# right_revision1_0.net
KiCad netlist of a schematic drawn in EAGLE
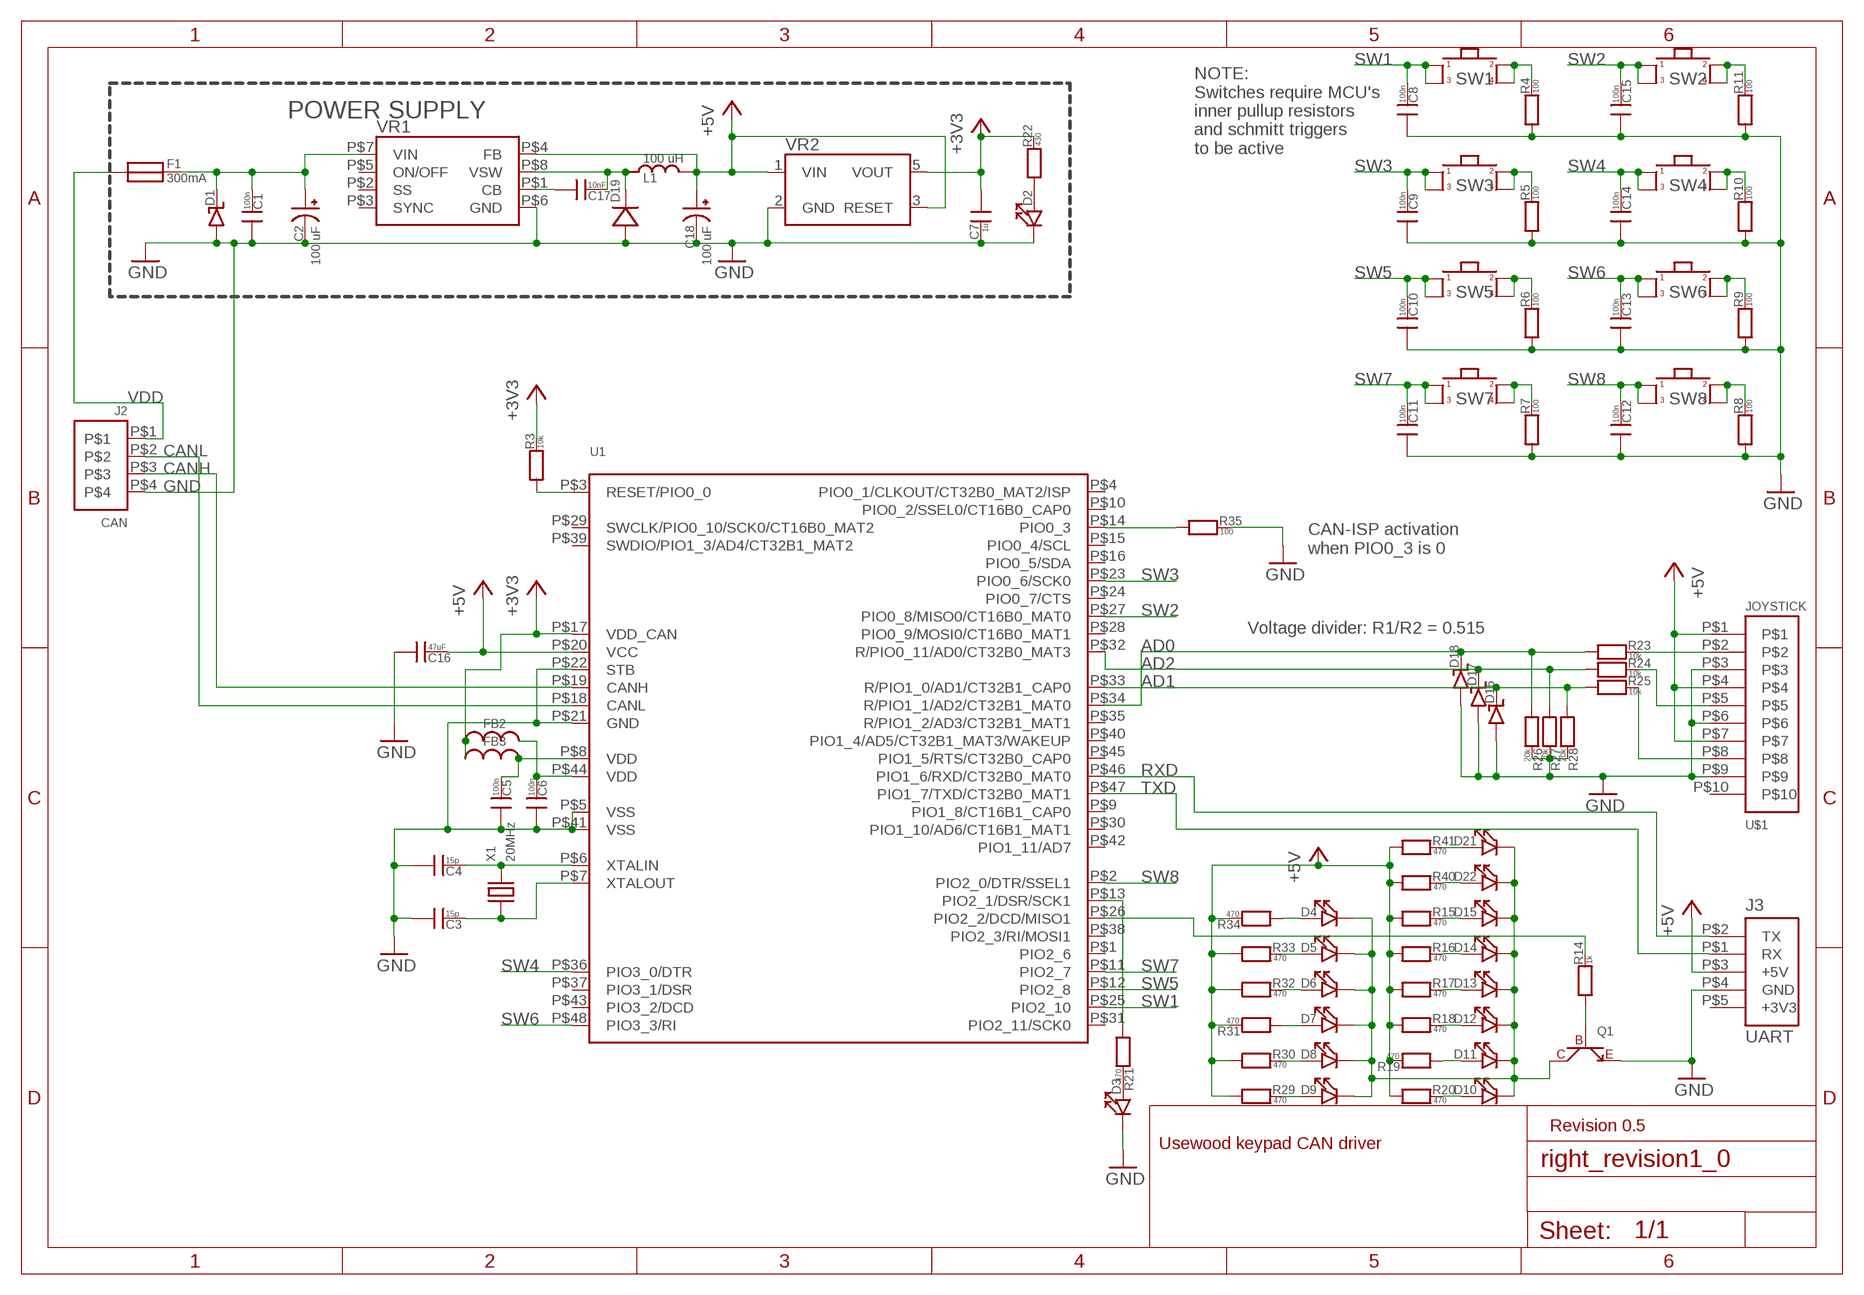
[diagram p0: schematic, sheet 1]

(export (version "E")
  (design (tool "Eeschema 10.0.6"))
  (components
    (comp (ref "C1")
      (value "100n")
      (footprint "eagle-import:0603_SILKSCREEN")
      (libsource (lib "eagle-import") (part "CAP0603_SILKSCREEN"))
    )
    (comp (ref "C2")
      (value "100 uF")
      (footprint "eagle-import:CAP_POL_SMD_10X10X10MM")
      (libsource (lib "eagle-import") (part "CAP_POLSMD_10X10X10MM"))
    )
    (comp (ref "C3")
      (value "15p")
      (footprint "eagle-import:0603_SILKSCREEN")
      (libsource (lib "eagle-import") (part "CAP0603_SILKSCREEN"))
    )
    (comp (ref "C4")
      (value "15p")
      (footprint "eagle-import:0603_SILKSCREEN")
      (libsource (lib "eagle-import") (part "CAP0603_SILKSCREEN"))
    )
    (comp (ref "C5")
      (value "100n")
      (footprint "eagle-import:0603_SILKSCREEN")
      (libsource (lib "eagle-import") (part "CAP0603_SILKSCREEN"))
    )
    (comp (ref "C6")
      (value "100n")
      (footprint "eagle-import:0603_SILKSCREEN")
      (libsource (lib "eagle-import") (part "CAP0603_SILKSCREEN"))
    )
    (comp (ref "C7")
      (value "1u")
      (footprint "eagle-import:0603_SILKSCREEN")
      (libsource (lib "eagle-import") (part "CAP0603_SILKSCREEN"))
    )
    (comp (ref "C8")
      (value "100n")
      (footprint "eagle-import:0603_SILKSCREEN")
      (libsource (lib "eagle-import") (part "CAP0603_SILKSCREEN"))
    )
    (comp (ref "C9")
      (value "100n")
      (footprint "eagle-import:0603_SILKSCREEN")
      (libsource (lib "eagle-import") (part "CAP0603_SILKSCREEN"))
    )
    (comp (ref "C10")
      (value "100n")
      (footprint "eagle-import:0603_SILKSCREEN")
      (libsource (lib "eagle-import") (part "CAP0603_SILKSCREEN"))
    )
    (comp (ref "C11")
      (value "100n")
      (footprint "eagle-import:0603_SILKSCREEN")
      (libsource (lib "eagle-import") (part "CAP0603_SILKSCREEN"))
    )
    (comp (ref "C12")
      (value "100n")
      (footprint "eagle-import:0603_SILKSCREEN")
      (libsource (lib "eagle-import") (part "CAP0603_SILKSCREEN"))
    )
    (comp (ref "C13")
      (value "100n")
      (footprint "eagle-import:0603_SILKSCREEN")
      (libsource (lib "eagle-import") (part "CAP0603_SILKSCREEN"))
    )
    (comp (ref "C14")
      (value "100n")
      (footprint "eagle-import:0603_SILKSCREEN")
      (libsource (lib "eagle-import") (part "CAP0603_SILKSCREEN"))
    )
    (comp (ref "C15")
      (value "100n")
      (footprint "eagle-import:0603_SILKSCREEN")
      (libsource (lib "eagle-import") (part "CAP0603_SILKSCREEN"))
    )
    (comp (ref "C16")
      (value "47uF")
      (footprint "eagle-import:0603_SILKSCREEN")
      (libsource (lib "eagle-import") (part "CAP0603_SILKSCREEN"))
    )
    (comp (ref "C17")
      (value "10nF")
      (footprint "eagle-import:0603_SILKSCREEN")
      (libsource (lib "eagle-import") (part "CAP0603_SILKSCREEN"))
    )
    (comp (ref "C18")
      (value "100 uF")
      (footprint "eagle-import:CAP_POL_SMD_10X10X10MM")
      (libsource (lib "eagle-import") (part "CAP_POLSMD_10X10X10MM"))
    )
    (comp (ref "D1")
      (value "DIODE_TVSDO-214AA")
      (footprint "eagle-import:DO-214AB")
      (libsource (lib "eagle-import") (part "DIODE_TVSDO-214AA"))
    )
    (comp (ref "D2")
      (value "LED0603_SILKSCREEN")
      (footprint "eagle-import:0603_SILKSCREEN")
      (libsource (lib "eagle-import") (part "LED0603_SILKSCREEN"))
    )
    (comp (ref "D3")
      (value "LED0603_SILKSCREEN")
      (footprint "eagle-import:0603_SILKSCREEN")
      (libsource (lib "eagle-import") (part "LED0603_SILKSCREEN"))
    )
    (comp (ref "D4")
      (value "LED0603_SILKSCREEN")
      (footprint "eagle-import:0603_SILKSCREEN")
      (libsource (lib "eagle-import") (part "LED0603_SILKSCREEN"))
    )
    (comp (ref "D5")
      (value "LED0603_SILKSCREEN")
      (footprint "eagle-import:0603_SILKSCREEN")
      (libsource (lib "eagle-import") (part "LED0603_SILKSCREEN"))
    )
    (comp (ref "D6")
      (value "LED0603_SILKSCREEN")
      (footprint "eagle-import:0603_SILKSCREEN")
      (libsource (lib "eagle-import") (part "LED0603_SILKSCREEN"))
    )
    (comp (ref "D7")
      (value "LED0603_SILKSCREEN")
      (footprint "eagle-import:0603_SILKSCREEN")
      (libsource (lib "eagle-import") (part "LED0603_SILKSCREEN"))
    )
    (comp (ref "D8")
      (value "LED0603_SILKSCREEN")
      (footprint "eagle-import:0603_SILKSCREEN")
      (libsource (lib "eagle-import") (part "LED0603_SILKSCREEN"))
    )
    (comp (ref "D9")
      (value "LED0603_SILKSCREEN")
      (footprint "eagle-import:0603_SILKSCREEN")
      (libsource (lib "eagle-import") (part "LED0603_SILKSCREEN"))
    )
    (comp (ref "D10")
      (value "LED0603_SILKSCREEN")
      (footprint "eagle-import:0603_SILKSCREEN")
      (libsource (lib "eagle-import") (part "LED0603_SILKSCREEN"))
    )
    (comp (ref "D11")
      (value "LED0603_SILKSCREEN")
      (footprint "eagle-import:0603_SILKSCREEN")
      (libsource (lib "eagle-import") (part "LED0603_SILKSCREEN"))
    )
    (comp (ref "D12")
      (value "LED0603_SILKSCREEN")
      (footprint "eagle-import:0603_SILKSCREEN")
      (libsource (lib "eagle-import") (part "LED0603_SILKSCREEN"))
    )
    (comp (ref "D13")
      (value "LED0603_SILKSCREEN")
      (footprint "eagle-import:0603_SILKSCREEN")
      (libsource (lib "eagle-import") (part "LED0603_SILKSCREEN"))
    )
    (comp (ref "D14")
      (value "LED0603_SILKSCREEN")
      (footprint "eagle-import:0603_SILKSCREEN")
      (libsource (lib "eagle-import") (part "LED0603_SILKSCREEN"))
    )
    (comp (ref "D15")
      (value "LED0603_SILKSCREEN")
      (footprint "eagle-import:0603_SILKSCREEN")
      (libsource (lib "eagle-import") (part "LED0603_SILKSCREEN"))
    )
    (comp (ref "D16")
      (value "DIODE_ZENERSDO123")
      (footprint "eagle-import:SOD123")
      (libsource (lib "eagle-import") (part "DIODE_ZENERSDO123"))
    )
    (comp (ref "D17")
      (value "DIODE_ZENERSDO123")
      (footprint "eagle-import:SOD123")
      (libsource (lib "eagle-import") (part "DIODE_ZENERSDO123"))
    )
    (comp (ref "D18")
      (value "DIODE_ZENERSDO123")
      (footprint "eagle-import:SOD123")
      (libsource (lib "eagle-import") (part "DIODE_ZENERSDO123"))
    )
    (comp (ref "D19")
      (value "DIODEDO219AB")
      (footprint "eagle-import:DO219AB")
      (libsource (lib "eagle-import") (part "DIODEDO219AB"))
    )
    (comp (ref "D21")
      (value "LED0603_SILKSCREEN")
      (footprint "eagle-import:0603_SILKSCREEN")
      (libsource (lib "eagle-import") (part "LED0603_SILKSCREEN"))
    )
    (comp (ref "D22")
      (value "LED0603_SILKSCREEN")
      (footprint "eagle-import:0603_SILKSCREEN")
      (libsource (lib "eagle-import") (part "LED0603_SILKSCREEN"))
    )
    (comp (ref "F1")
      (value "300mA")
      (footprint "eagle-import:FUSE_100MA")
      (libsource (lib "eagle-import") (part "FUSE100MA"))
    )
    (comp (ref "FB2")
      (value "FERRITE0603_SILKSCREEN")
      (footprint "eagle-import:0603_SILKSCREEN")
      (libsource (lib "eagle-import") (part "FERRITE0603_SILKSCREEN"))
    )
    (comp (ref "FB3")
      (value "FERRITE0603_SILKSCREEN")
      (footprint "eagle-import:0603_SILKSCREEN")
      (libsource (lib "eagle-import") (part "FERRITE0603_SILKSCREEN"))
    )
    (comp (ref "J2")
      (value "CAN")
      (footprint "eagle-import:MOLEX_MICRO-FIT_4WAY")
      (libsource (lib "eagle-import") (part "MOLEX_MICRO-FIT_4WAYTH"))
    )
    (comp (ref "J3")
      (value "UART")
      (footprint "eagle-import:HEADER5_1")
      (libsource (lib "eagle-import") (part "HEADER_USARTTH"))
    )
    (comp (ref "L1")
      (value "100 uH")
      (footprint "eagle-import:INDUCTOR_BOURNS_10X13X5MM")
      (libsource (lib "eagle-import") (part "INDUCTORBOURNS_10X13X5MM"))
    )
    (comp (ref "Q1")
      (value "NPN_TRANSISTORSOT323")
      (footprint "eagle-import:SOT323")
      (libsource (lib "eagle-import") (part "NPN_TRANSISTORSOT323"))
    )
    (comp (ref "R3")
      (value "10k")
      (footprint "eagle-import:0603_SILKSCREEN")
      (libsource (lib "eagle-import") (part "RES0604_SILKSCREEN"))
    )
    (comp (ref "R4")
      (value "100")
      (footprint "eagle-import:0603_SILKSCREEN")
      (libsource (lib "eagle-import") (part "RES0604_SILKSCREEN"))
    )
    (comp (ref "R5")
      (value "100")
      (footprint "eagle-import:0603_SILKSCREEN")
      (libsource (lib "eagle-import") (part "RES0604_SILKSCREEN"))
    )
    (comp (ref "R6")
      (value "100")
      (footprint "eagle-import:0603_SILKSCREEN")
      (libsource (lib "eagle-import") (part "RES0604_SILKSCREEN"))
    )
    (comp (ref "R7")
      (value "100")
      (footprint "eagle-import:0603_SILKSCREEN")
      (libsource (lib "eagle-import") (part "RES0604_SILKSCREEN"))
    )
    (comp (ref "R8")
      (value "100")
      (footprint "eagle-import:0603_SILKSCREEN")
      (libsource (lib "eagle-import") (part "RES0604_SILKSCREEN"))
    )
    (comp (ref "R9")
      (value "100")
      (footprint "eagle-import:0603_SILKSCREEN")
      (libsource (lib "eagle-import") (part "RES0604_SILKSCREEN"))
    )
    (comp (ref "R10")
      (value "100")
      (footprint "eagle-import:0603_SILKSCREEN")
      (libsource (lib "eagle-import") (part "RES0604_SILKSCREEN"))
    )
    (comp (ref "R11")
      (value "100")
      (footprint "eagle-import:0603_SILKSCREEN")
      (libsource (lib "eagle-import") (part "RES0604_SILKSCREEN"))
    )
    (comp (ref "R14")
      (value "1k")
      (footprint "eagle-import:0603_SILKSCREEN")
      (libsource (lib "eagle-import") (part "RES0604_SILKSCREEN"))
    )
    (comp (ref "R15")
      (value "470")
      (footprint "eagle-import:0603_SILKSCREEN")
      (libsource (lib "eagle-import") (part "RES0604_SILKSCREEN"))
    )
    (comp (ref "R16")
      (value "470")
      (footprint "eagle-import:0603_SILKSCREEN")
      (libsource (lib "eagle-import") (part "RES0604_SILKSCREEN"))
    )
    (comp (ref "R17")
      (value "470")
      (footprint "eagle-import:0603_SILKSCREEN")
      (libsource (lib "eagle-import") (part "RES0604_SILKSCREEN"))
    )
    (comp (ref "R18")
      (value "470")
      (footprint "eagle-import:0603_SILKSCREEN")
      (libsource (lib "eagle-import") (part "RES0604_SILKSCREEN"))
    )
    (comp (ref "R19")
      (value "470")
      (footprint "eagle-import:0603_SILKSCREEN")
      (libsource (lib "eagle-import") (part "RES0604_SILKSCREEN"))
    )
    (comp (ref "R20")
      (value "470")
      (footprint "eagle-import:0603_SILKSCREEN")
      (libsource (lib "eagle-import") (part "RES0604_SILKSCREEN"))
    )
    (comp (ref "R21")
      (value "470")
      (footprint "eagle-import:0603_SILKSCREEN")
      (libsource (lib "eagle-import") (part "RES0604_SILKSCREEN"))
    )
    (comp (ref "R22")
      (value "430")
      (footprint "eagle-import:0603_SILKSCREEN")
      (libsource (lib "eagle-import") (part "RES0604_SILKSCREEN"))
    )
    (comp (ref "R23")
      (value "10k")
      (footprint "eagle-import:0603_SILKSCREEN")
      (libsource (lib "eagle-import") (part "RES0604_SILKSCREEN"))
    )
    (comp (ref "R24")
      (value "10k")
      (footprint "eagle-import:0603_SILKSCREEN")
      (libsource (lib "eagle-import") (part "RES0604_SILKSCREEN"))
    )
    (comp (ref "R25")
      (value "10k")
      (footprint "eagle-import:0603_SILKSCREEN")
      (libsource (lib "eagle-import") (part "RES0604_SILKSCREEN"))
    )
    (comp (ref "R26")
      (value "20k")
      (footprint "eagle-import:0603_SILKSCREEN")
      (libsource (lib "eagle-import") (part "RES0604_SILKSCREEN"))
    )
    (comp (ref "R27")
      (value "20k")
      (footprint "eagle-import:0603_SILKSCREEN")
      (libsource (lib "eagle-import") (part "RES0604_SILKSCREEN"))
    )
    (comp (ref "R28")
      (value "20k")
      (footprint "eagle-import:0603_SILKSCREEN")
      (libsource (lib "eagle-import") (part "RES0604_SILKSCREEN"))
    )
    (comp (ref "R29")
      (value "470")
      (footprint "eagle-import:0603_SILKSCREEN")
      (libsource (lib "eagle-import") (part "RES0604_SILKSCREEN"))
    )
    (comp (ref "R30")
      (value "470")
      (footprint "eagle-import:0603_SILKSCREEN")
      (libsource (lib "eagle-import") (part "RES0604_SILKSCREEN"))
    )
    (comp (ref "R31")
      (value "470")
      (footprint "eagle-import:0603_SILKSCREEN")
      (libsource (lib "eagle-import") (part "RES0604_SILKSCREEN"))
    )
    (comp (ref "R32")
      (value "470")
      (footprint "eagle-import:0603_SILKSCREEN")
      (libsource (lib "eagle-import") (part "RES0604_SILKSCREEN"))
    )
    (comp (ref "R33")
      (value "470")
      (footprint "eagle-import:0603_SILKSCREEN")
      (libsource (lib "eagle-import") (part "RES0604_SILKSCREEN"))
    )
    (comp (ref "R34")
      (value "470")
      (footprint "eagle-import:0603_SILKSCREEN")
      (libsource (lib "eagle-import") (part "RES0604_SILKSCREEN"))
    )
    (comp (ref "R35")
      (value "100")
      (footprint "eagle-import:0603_SILKSCREEN")
      (libsource (lib "eagle-import") (part "RES0604_SILKSCREEN"))
    )
    (comp (ref "R40")
      (value "470")
      (footprint "eagle-import:0603_SILKSCREEN")
      (libsource (lib "eagle-import") (part "RES0604_SILKSCREEN"))
    )
    (comp (ref "R41")
      (value "470")
      (footprint "eagle-import:0603_SILKSCREEN")
      (libsource (lib "eagle-import") (part "RES0604_SILKSCREEN"))
    )
    (comp (ref "SW1")
      (value "SWITCH12X12MM_CENTER_HOLE")
      (footprint "eagle-import:SWITCH_12X12MM_CENTER_HOLE")
      (libsource (lib "eagle-import") (part "SWITCH12X12MM_CENTER_HOLE"))
    )
    (comp (ref "SW2")
      (value "SWITCH12X12MM_CENTER_HOLE")
      (footprint "eagle-import:SWITCH_12X12MM_CENTER_HOLE")
      (libsource (lib "eagle-import") (part "SWITCH12X12MM_CENTER_HOLE"))
    )
    (comp (ref "SW3")
      (value "SWITCH12X12MM_CENTER_HOLE")
      (footprint "eagle-import:SWITCH_12X12MM_CENTER_HOLE")
      (libsource (lib "eagle-import") (part "SWITCH12X12MM_CENTER_HOLE"))
    )
    (comp (ref "SW4")
      (value "SWITCH12X12MM_CENTER_HOLE")
      (footprint "eagle-import:SWITCH_12X12MM_CENTER_HOLE")
      (libsource (lib "eagle-import") (part "SWITCH12X12MM_CENTER_HOLE"))
    )
    (comp (ref "SW5")
      (value "SWITCH12X12MM_CENTER_HOLE")
      (footprint "eagle-import:SWITCH_12X12MM_CENTER_HOLE")
      (libsource (lib "eagle-import") (part "SWITCH12X12MM_CENTER_HOLE"))
    )
    (comp (ref "SW6")
      (value "SWITCH12X12MM_CENTER_HOLE")
      (footprint "eagle-import:SWITCH_12X12MM_CENTER_HOLE")
      (libsource (lib "eagle-import") (part "SWITCH12X12MM_CENTER_HOLE"))
    )
    (comp (ref "SW7")
      (value "SWITCH12X12MM_CENTER_HOLE")
      (footprint "eagle-import:SWITCH_12X12MM_CENTER_HOLE")
      (libsource (lib "eagle-import") (part "SWITCH12X12MM_CENTER_HOLE"))
    )
    (comp (ref "SW8")
      (value "SWITCH12X12MM_CENTER_HOLE")
      (footprint "eagle-import:SWITCH_12X12MM_CENTER_HOLE")
      (libsource (lib "eagle-import") (part "SWITCH12X12MM_CENTER_HOLE"))
    )
    (comp (ref "U$1")
      (value "JOYSTICK")
      (footprint "eagle-import:MOLEX-MICRO-FIT_10WAY")
      (libsource (lib "eagle-import") (part "MOLEX_MICRO-FIT_10WAYTH"))
    )
    (comp (ref "U1")
      (value "LPC11C22QFP48")
      (footprint "eagle-import:QFP48")
      (libsource (lib "eagle-import") (part "LPC11C22QFP48"))
    )
    (comp (ref "VR1")
      (value "LM2671SOIC8")
      (footprint "eagle-import:SOIC8")
      (libsource (lib "eagle-import") (part "LM2671SOIC8"))
    )
    (comp (ref "VR2")
      (value "LP2985SOP5")
      (footprint "eagle-import:SOP5")
      (libsource (lib "eagle-import") (part "LP2985SOP5"))
    )
    (comp (ref "X1")
      (value "20MHz")
      (footprint "eagle-import:XTAL_SMD_5X3.2")
      (libsource (lib "eagle-import") (part "XTALSMD_5X3.2"))
    )
  )
  (nets
    (net (code "1") (name "+3V3") (class "Default")
      (node (ref "C7") (pin "0") (pinfunction "P$1_0") (pintype "bidirectional"))
      (node (ref "FB2") (pin "0") (pinfunction "P$1_0") (pintype "bidirectional"))
      (node (ref "FB3") (pin "0") (pinfunction "P$1_0") (pintype "bidirectional"))
      (node (ref "R22") (pin "1") (pinfunction "P$2_1") (pintype "bidirectional"))
      (node (ref "R3") (pin "1") (pinfunction "P$2_1") (pintype "bidirectional"))
      (node (ref "U1") (pin "P$17") (pinfunction "VDD_CAN_P$17") (pintype "bidirectional"))
      (node (ref "VR2") (pin "5") (pinfunction "VOUT_5") (pintype "bidirectional"))
    )
    (net (code "2") (name "+5V") (class "Default")
      (node (ref "C16") (pin "1") (pinfunction "P$2_1") (pintype "bidirectional"))
      (node (ref "C18") (pin "+") (pinfunction "+_+") (pintype "bidirectional"))
      (node (ref "J3") (pin "P$3") (pinfunction "+5V_P$3") (pintype "bidirectional"))
      (node (ref "L1") (pin "P$2") (pinfunction "P$2_P$2") (pintype "bidirectional"))
      (node (ref "R15") (pin "0") (pinfunction "P$1_0") (pintype "bidirectional"))
      (node (ref "R16") (pin "0") (pinfunction "P$1_0") (pintype "bidirectional"))
      (node (ref "R17") (pin "0") (pinfunction "P$1_0") (pintype "bidirectional"))
      (node (ref "R18") (pin "0") (pinfunction "P$1_0") (pintype "bidirectional"))
      (node (ref "R19") (pin "1") (pinfunction "P$2_1") (pintype "bidirectional"))
      (node (ref "R20") (pin "0") (pinfunction "P$1_0") (pintype "bidirectional"))
      (node (ref "R29") (pin "0") (pinfunction "P$1_0") (pintype "bidirectional"))
      (node (ref "R30") (pin "0") (pinfunction "P$1_0") (pintype "bidirectional"))
      (node (ref "R31") (pin "1") (pinfunction "P$2_1") (pintype "bidirectional"))
      (node (ref "R32") (pin "0") (pinfunction "P$1_0") (pintype "bidirectional"))
      (node (ref "R33") (pin "0") (pinfunction "P$1_0") (pintype "bidirectional"))
      (node (ref "R34") (pin "1") (pinfunction "P$2_1") (pintype "bidirectional"))
      (node (ref "R40") (pin "0") (pinfunction "P$1_0") (pintype "bidirectional"))
      (node (ref "R41") (pin "0") (pinfunction "P$1_0") (pintype "bidirectional"))
      (node (ref "U$1") (pin "P$1") (pinfunction "P$1_P$1") (pintype "bidirectional"))
      (node (ref "U$1") (pin "P$4") (pinfunction "P$4_P$4") (pintype "bidirectional"))
      (node (ref "U$1") (pin "P$7") (pinfunction "P$7_P$7") (pintype "bidirectional"))
      (node (ref "U1") (pin "P$20") (pinfunction "VCC_P$20") (pintype "bidirectional"))
      (node (ref "VR1") (pin "P$4") (pinfunction "FB_P$4") (pintype "bidirectional"))
      (node (ref "VR2") (pin "1") (pinfunction "VIN_1") (pintype "bidirectional"))
      (node (ref "VR2") (pin "3") (pinfunction "RESET_3") (pintype "bidirectional"))
    )
    (net (code "3") (name "/AD0") (class "Default")
      (node (ref "D18") (pin "P$2") (pinfunction "N_P$2") (pintype "bidirectional"))
      (node (ref "R23") (pin "0") (pinfunction "P$1_0") (pintype "bidirectional"))
      (node (ref "R26") (pin "0") (pinfunction "P$1_0") (pintype "bidirectional"))
      (node (ref "U1") (pin "P$34") (pinfunction "R/PIO1_1/AD2/CT32B1_MAT0_P$34") (pintype "bidirectional"))
    )
    (net (code "4") (name "/AD1") (class "Default")
      (node (ref "D16") (pin "P$2") (pinfunction "N_P$2") (pintype "bidirectional"))
      (node (ref "R25") (pin "0") (pinfunction "P$1_0") (pintype "bidirectional"))
      (node (ref "R28") (pin "0") (pinfunction "P$1_0") (pintype "bidirectional"))
      (node (ref "U1") (pin "P$33") (pinfunction "R/PIO1_0/AD1/CT32B1_CAP0_P$33") (pintype "bidirectional"))
    )
    (net (code "5") (name "/AD2") (class "Default")
      (node (ref "D17") (pin "P$2") (pinfunction "N_P$2") (pintype "bidirectional"))
      (node (ref "R24") (pin "0") (pinfunction "P$1_0") (pintype "bidirectional"))
      (node (ref "R27") (pin "0") (pinfunction "P$1_0") (pintype "bidirectional"))
      (node (ref "U1") (pin "P$32") (pinfunction "R/PIO0_11/AD0/CT32B0_MAT3_P$32") (pintype "bidirectional"))
    )
    (net (code "6") (name "/CANH") (class "Default")
      (node (ref "J2") (pin "P$3") (pinfunction "P$3_P$3") (pintype "bidirectional"))
      (node (ref "U1") (pin "P$19") (pinfunction "CANH_P$19") (pintype "bidirectional"))
    )
    (net (code "7") (name "/CANL") (class "Default")
      (node (ref "J2") (pin "P$2") (pinfunction "P$2_P$2") (pintype "bidirectional"))
      (node (ref "U1") (pin "P$18") (pinfunction "CANL_P$18") (pintype "bidirectional"))
    )
    (net (code "8") (name "/RXD") (class "Default")
      (node (ref "J3") (pin "P$2") (pinfunction "TX_P$2") (pintype "bidirectional"))
      (node (ref "U1") (pin "P$46") (pinfunction "PIO1_6/RXD/CT32B0_MAT0_P$46") (pintype "bidirectional"))
    )
    (net (code "9") (name "/SW1") (class "Default")
      (node (ref "C8") (pin "1") (pinfunction "P$2_1") (pintype "bidirectional"))
      (node (ref "SW1") (pin "P$1") (pinfunction "P$1_P$1") (pintype "bidirectional"))
      (node (ref "SW1") (pin "P$2") (pinfunction "P$3_P$2") (pintype "bidirectional"))
      (node (ref "U1") (pin "P$25") (pinfunction "PIO2_10_P$25") (pintype "bidirectional"))
    )
    (net (code "10") (name "/SW2") (class "Default")
      (node (ref "C15") (pin "1") (pinfunction "P$2_1") (pintype "bidirectional"))
      (node (ref "SW2") (pin "P$1") (pinfunction "P$1_P$1") (pintype "bidirectional"))
      (node (ref "SW2") (pin "P$2") (pinfunction "P$3_P$2") (pintype "bidirectional"))
      (node (ref "U1") (pin "P$27") (pinfunction "PIO0_8/MISO0/CT16B0_MAT0_P$27") (pintype "bidirectional"))
    )
    (net (code "11") (name "/SW3") (class "Default")
      (node (ref "C9") (pin "1") (pinfunction "P$2_1") (pintype "bidirectional"))
      (node (ref "SW3") (pin "P$1") (pinfunction "P$1_P$1") (pintype "bidirectional"))
      (node (ref "SW3") (pin "P$2") (pinfunction "P$3_P$2") (pintype "bidirectional"))
      (node (ref "U1") (pin "P$23") (pinfunction "PIO0_6/SCK0_P$23") (pintype "bidirectional"))
    )
    (net (code "12") (name "/SW4") (class "Default")
      (node (ref "C14") (pin "1") (pinfunction "P$2_1") (pintype "bidirectional"))
      (node (ref "SW4") (pin "P$1") (pinfunction "P$1_P$1") (pintype "bidirectional"))
      (node (ref "SW4") (pin "P$2") (pinfunction "P$3_P$2") (pintype "bidirectional"))
      (node (ref "U1") (pin "P$36") (pinfunction "PIO3_0/DTR_P$36") (pintype "bidirectional"))
    )
    (net (code "13") (name "/SW5") (class "Default")
      (node (ref "C10") (pin "1") (pinfunction "P$2_1") (pintype "bidirectional"))
      (node (ref "SW5") (pin "P$1") (pinfunction "P$1_P$1") (pintype "bidirectional"))
      (node (ref "SW5") (pin "P$2") (pinfunction "P$3_P$2") (pintype "bidirectional"))
      (node (ref "U1") (pin "P$12") (pinfunction "PIO2_8_P$12") (pintype "bidirectional"))
    )
    (net (code "14") (name "/SW6") (class "Default")
      (node (ref "C13") (pin "1") (pinfunction "P$2_1") (pintype "bidirectional"))
      (node (ref "SW6") (pin "P$1") (pinfunction "P$1_P$1") (pintype "bidirectional"))
      (node (ref "SW6") (pin "P$2") (pinfunction "P$3_P$2") (pintype "bidirectional"))
      (node (ref "U1") (pin "P$48") (pinfunction "PIO3_3/RI_P$48") (pintype "bidirectional"))
    )
    (net (code "15") (name "/SW7") (class "Default")
      (node (ref "C11") (pin "1") (pinfunction "P$2_1") (pintype "bidirectional"))
      (node (ref "SW7") (pin "P$1") (pinfunction "P$1_P$1") (pintype "bidirectional"))
      (node (ref "SW7") (pin "P$2") (pinfunction "P$3_P$2") (pintype "bidirectional"))
      (node (ref "U1") (pin "P$11") (pinfunction "PIO2_7_P$11") (pintype "bidirectional"))
    )
    (net (code "16") (name "/SW8") (class "Default")
      (node (ref "C12") (pin "1") (pinfunction "P$2_1") (pintype "bidirectional"))
      (node (ref "SW8") (pin "P$1") (pinfunction "P$1_P$1") (pintype "bidirectional"))
      (node (ref "SW8") (pin "P$2") (pinfunction "P$3_P$2") (pintype "bidirectional"))
      (node (ref "U1") (pin "P$2") (pinfunction "PIO2_0/DTR/SSEL1_P$2") (pintype "bidirectional"))
    )
    (net (code "17") (name "/TXD") (class "Default")
      (node (ref "J3") (pin "P$1") (pinfunction "RX_P$1") (pintype "bidirectional"))
      (node (ref "U1") (pin "P$47") (pinfunction "PIO1_7/TXD/CT32B0_MAT1_P$47") (pintype "bidirectional"))
    )
    (net (code "18") (name "/VDD") (class "Default")
      (node (ref "F1") (pin "P$1") (pinfunction "P$1_P$1") (pintype "bidirectional"))
      (node (ref "J2") (pin "P$1") (pinfunction "P$1_P$1") (pintype "bidirectional"))
    )
    (net (code "19") (name "GND") (class "Default")
      (node (ref "C1") (pin "0") (pinfunction "P$1_0") (pintype "bidirectional"))
      (node (ref "C10") (pin "0") (pinfunction "P$1_0") (pintype "bidirectional"))
      (node (ref "C11") (pin "0") (pinfunction "P$1_0") (pintype "bidirectional"))
      (node (ref "C12") (pin "0") (pinfunction "P$1_0") (pintype "bidirectional"))
      (node (ref "C13") (pin "0") (pinfunction "P$1_0") (pintype "bidirectional"))
      (node (ref "C14") (pin "0") (pinfunction "P$1_0") (pintype "bidirectional"))
      (node (ref "C15") (pin "0") (pinfunction "P$1_0") (pintype "bidirectional"))
      (node (ref "C16") (pin "0") (pinfunction "P$1_0") (pintype "bidirectional"))
      (node (ref "C18") (pin "-") (pinfunction "-_-") (pintype "bidirectional"))
      (node (ref "C2") (pin "-") (pinfunction "-_-") (pintype "bidirectional"))
      (node (ref "C3") (pin "0") (pinfunction "P$1_0") (pintype "bidirectional"))
      (node (ref "C4") (pin "0") (pinfunction "P$1_0") (pintype "bidirectional"))
      (node (ref "C5") (pin "0") (pinfunction "P$1_0") (pintype "bidirectional"))
      (node (ref "C6") (pin "0") (pinfunction "P$1_0") (pintype "bidirectional"))
      (node (ref "C7") (pin "1") (pinfunction "P$2_1") (pintype "bidirectional"))
      (node (ref "C8") (pin "0") (pinfunction "P$1_0") (pintype "bidirectional"))
      (node (ref "C9") (pin "0") (pinfunction "P$1_0") (pintype "bidirectional"))
      (node (ref "D1") (pin "P$1") (pinfunction "P_P$1") (pintype "bidirectional"))
      (node (ref "D16") (pin "P$1") (pinfunction "P_P$1") (pintype "bidirectional"))
      (node (ref "D17") (pin "P$1") (pinfunction "P_P$1") (pintype "bidirectional"))
      (node (ref "D18") (pin "P$1") (pinfunction "P_P$1") (pintype "bidirectional"))
      (node (ref "D19") (pin "P$1") (pinfunction "P_P$1") (pintype "bidirectional"))
      (node (ref "D2") (pin "1") (pinfunction "1_1") (pintype "bidirectional"))
      (node (ref "D3") (pin "1") (pinfunction "1_1") (pintype "bidirectional"))
      (node (ref "J2") (pin "P$4") (pinfunction "P$4_P$4") (pintype "bidirectional"))
      (node (ref "J3") (pin "P$4") (pinfunction "GND_P$4") (pintype "bidirectional"))
      (node (ref "Q1") (pin "R") (pinfunction "E_R") (pintype "bidirectional"))
      (node (ref "R10") (pin "0") (pinfunction "P$1_0") (pintype "bidirectional"))
      (node (ref "R11") (pin "0") (pinfunction "P$1_0") (pintype "bidirectional"))
      (node (ref "R26") (pin "1") (pinfunction "P$2_1") (pintype "bidirectional"))
      (node (ref "R27") (pin "1") (pinfunction "P$2_1") (pintype "bidirectional"))
      (node (ref "R28") (pin "1") (pinfunction "P$2_1") (pintype "bidirectional"))
      (node (ref "R35") (pin "1") (pinfunction "P$2_1") (pintype "bidirectional"))
      (node (ref "R4") (pin "0") (pinfunction "P$1_0") (pintype "bidirectional"))
      (node (ref "R5") (pin "0") (pinfunction "P$1_0") (pintype "bidirectional"))
      (node (ref "R6") (pin "0") (pinfunction "P$1_0") (pintype "bidirectional"))
      (node (ref "R7") (pin "0") (pinfunction "P$1_0") (pintype "bidirectional"))
      (node (ref "R8") (pin "0") (pinfunction "P$1_0") (pintype "bidirectional"))
      (node (ref "R9") (pin "0") (pinfunction "P$1_0") (pintype "bidirectional"))
      (node (ref "U$1") (pin "P$3") (pinfunction "P$3_P$3") (pintype "bidirectional"))
      (node (ref "U$1") (pin "P$6") (pinfunction "P$6_P$6") (pintype "bidirectional"))
      (node (ref "U$1") (pin "P$9") (pinfunction "P$9_P$9") (pintype "bidirectional"))
      (node (ref "U1") (pin "P$21") (pinfunction "GND_P$21") (pintype "bidirectional"))
      (node (ref "U1") (pin "P$22") (pinfunction "STB_P$22") (pintype "bidirectional"))
      (node (ref "U1") (pin "P$41") (pinfunction "VSS_P$41") (pintype "bidirectional"))
      (node (ref "U1") (pin "P$5") (pinfunction "VSS_P$5") (pintype "bidirectional"))
      (node (ref "VR1") (pin "P$6") (pinfunction "GND_P$6") (pintype "bidirectional"))
      (node (ref "VR2") (pin "2") (pinfunction "GND_2") (pintype "bidirectional"))
    )
    (net (code "20") (name "Net-(C1-P$2)") (class "Default")
      (node (ref "C1") (pin "1") (pinfunction "P$2_1") (pintype "bidirectional"))
      (node (ref "C2") (pin "+") (pinfunction "+_+") (pintype "bidirectional"))
      (node (ref "D1") (pin "P$2") (pinfunction "N_P$2") (pintype "bidirectional"))
      (node (ref "F1") (pin "P$2") (pinfunction "P$2_P$2") (pintype "bidirectional"))
      (node (ref "VR1") (pin "P$7") (pinfunction "VIN_P$7") (pintype "bidirectional"))
    )
    (net (code "21") (name "Net-(C3-P$2)") (class "Default")
      (node (ref "C3") (pin "1") (pinfunction "P$2_1") (pintype "bidirectional"))
      (node (ref "U1") (pin "P$7") (pinfunction "XTALOUT_P$7") (pintype "bidirectional"))
      (node (ref "X1") (pin "P$1") (pinfunction "P$1_P$1") (pintype "bidirectional"))
    )
    (net (code "22") (name "Net-(C4-P$2)") (class "Default")
      (node (ref "C4") (pin "1") (pinfunction "P$2_1") (pintype "bidirectional"))
      (node (ref "U1") (pin "P$6") (pinfunction "XTALIN_P$6") (pintype "bidirectional"))
      (node (ref "X1") (pin "P$2") (pinfunction "P$2_P$2") (pintype "bidirectional"))
    )
    (net (code "23") (name "Net-(C5-P$2)") (class "Default")
      (node (ref "C5") (pin "1") (pinfunction "P$2_1") (pintype "bidirectional"))
      (node (ref "FB3") (pin "1") (pinfunction "P$2_1") (pintype "bidirectional"))
      (node (ref "U1") (pin "P$8") (pinfunction "VDD_P$8") (pintype "bidirectional"))
    )
    (net (code "24") (name "Net-(C6-P$2)") (class "Default")
      (node (ref "C6") (pin "1") (pinfunction "P$2_1") (pintype "bidirectional"))
      (node (ref "FB2") (pin "1") (pinfunction "P$2_1") (pintype "bidirectional"))
      (node (ref "U1") (pin "P$44") (pinfunction "VDD_P$44") (pintype "bidirectional"))
    )
    (net (code "25") (name "Net-(C17-P$1)") (class "Default")
      (node (ref "C17") (pin "0") (pinfunction "P$1_0") (pintype "bidirectional"))
      (node (ref "VR1") (pin "P$1") (pinfunction "CB_P$1") (pintype "bidirectional"))
    )
    (net (code "26") (name "Net-(C17-P$2)") (class "Default")
      (node (ref "C17") (pin "1") (pinfunction "P$2_1") (pintype "bidirectional"))
      (node (ref "D19") (pin "P$2") (pinfunction "N_P$2") (pintype "bidirectional"))
      (node (ref "L1") (pin "P$1") (pinfunction "P$1_P$1") (pintype "bidirectional"))
      (node (ref "VR1") (pin "P$8") (pinfunction "VSW_P$8") (pintype "bidirectional"))
    )
    (net (code "27") (name "Net-(Q1-B)") (class "Default")
      (node (ref "Q1") (pin "L") (pinfunction "B_L") (pintype "bidirectional"))
      (node (ref "R14") (pin "0") (pinfunction "P$1_0") (pintype "bidirectional"))
    )
    (net (code "28") (name "Net-(Q1-C)") (class "Default")
      (node (ref "D10") (pin "1") (pinfunction "1_1") (pintype "bidirectional"))
      (node (ref "D11") (pin "1") (pinfunction "1_1") (pintype "bidirectional"))
      (node (ref "D12") (pin "1") (pinfunction "1_1") (pintype "bidirectional"))
      (node (ref "D13") (pin "1") (pinfunction "1_1") (pintype "bidirectional"))
      (node (ref "D14") (pin "1") (pinfunction "1_1") (pintype "bidirectional"))
      (node (ref "D15") (pin "1") (pinfunction "1_1") (pintype "bidirectional"))
      (node (ref "D21") (pin "1") (pinfunction "1_1") (pintype "bidirectional"))
      (node (ref "D22") (pin "1") (pinfunction "1_1") (pintype "bidirectional"))
      (node (ref "D4") (pin "1") (pinfunction "1_1") (pintype "bidirectional"))
      (node (ref "D5") (pin "1") (pinfunction "1_1") (pintype "bidirectional"))
      (node (ref "D6") (pin "1") (pinfunction "1_1") (pintype "bidirectional"))
      (node (ref "D7") (pin "1") (pinfunction "1_1") (pintype "bidirectional"))
      (node (ref "D8") (pin "1") (pinfunction "1_1") (pintype "bidirectional"))
      (node (ref "D9") (pin "1") (pinfunction "1_1") (pintype "bidirectional"))
      (node (ref "Q1") (pin "M") (pinfunction "C_M") (pintype "bidirectional"))
    )
    (net (code "29") (name "Net-(R3-P$1)") (class "Default")
      (node (ref "R3") (pin "0") (pinfunction "P$1_0") (pintype "bidirectional"))
      (node (ref "U1") (pin "P$3") (pinfunction "RESET/PIO0_0_P$3") (pintype "bidirectional"))
    )
    (net (code "30") (name "Net-(R4-P$2)") (class "Default")
      (node (ref "R4") (pin "1") (pinfunction "P$2_1") (pintype "bidirectional"))
      (node (ref "SW1") (pin "P$3") (pinfunction "P$2_P$3") (pintype "bidirectional"))
      (node (ref "SW1") (pin "P$4") (pinfunction "P$4_P$4") (pintype "bidirectional"))
    )
    (net (code "31") (name "Net-(R5-P$2)") (class "Default")
      (node (ref "R5") (pin "1") (pinfunction "P$2_1") (pintype "bidirectional"))
      (node (ref "SW3") (pin "P$3") (pinfunction "P$2_P$3") (pintype "bidirectional"))
      (node (ref "SW3") (pin "P$4") (pinfunction "P$4_P$4") (pintype "bidirectional"))
    )
    (net (code "32") (name "Net-(R6-P$2)") (class "Default")
      (node (ref "R6") (pin "1") (pinfunction "P$2_1") (pintype "bidirectional"))
      (node (ref "SW5") (pin "P$3") (pinfunction "P$2_P$3") (pintype "bidirectional"))
      (node (ref "SW5") (pin "P$4") (pinfunction "P$4_P$4") (pintype "bidirectional"))
    )
    (net (code "33") (name "Net-(R7-P$2)") (class "Default")
      (node (ref "R7") (pin "1") (pinfunction "P$2_1") (pintype "bidirectional"))
      (node (ref "SW7") (pin "P$3") (pinfunction "P$2_P$3") (pintype "bidirectional"))
      (node (ref "SW7") (pin "P$4") (pinfunction "P$4_P$4") (pintype "bidirectional"))
    )
    (net (code "34") (name "Net-(R8-P$2)") (class "Default")
      (node (ref "R8") (pin "1") (pinfunction "P$2_1") (pintype "bidirectional"))
      (node (ref "SW8") (pin "P$3") (pinfunction "P$2_P$3") (pintype "bidirectional"))
      (node (ref "SW8") (pin "P$4") (pinfunction "P$4_P$4") (pintype "bidirectional"))
    )
    (net (code "35") (name "Net-(R9-P$2)") (class "Default")
      (node (ref "R9") (pin "1") (pinfunction "P$2_1") (pintype "bidirectional"))
      (node (ref "SW6") (pin "P$3") (pinfunction "P$2_P$3") (pintype "bidirectional"))
      (node (ref "SW6") (pin "P$4") (pinfunction "P$4_P$4") (pintype "bidirectional"))
    )
    (net (code "36") (name "Net-(R10-P$2)") (class "Default")
      (node (ref "R10") (pin "1") (pinfunction "P$2_1") (pintype "bidirectional"))
      (node (ref "SW4") (pin "P$3") (pinfunction "P$2_P$3") (pintype "bidirectional"))
      (node (ref "SW4") (pin "P$4") (pinfunction "P$4_P$4") (pintype "bidirectional"))
    )
    (net (code "37") (name "Net-(R11-P$2)") (class "Default")
      (node (ref "R11") (pin "1") (pinfunction "P$2_1") (pintype "bidirectional"))
      (node (ref "SW2") (pin "P$3") (pinfunction "P$2_P$3") (pintype "bidirectional"))
      (node (ref "SW2") (pin "P$4") (pinfunction "P$4_P$4") (pintype "bidirectional"))
    )
    (net (code "38") (name "Net-(R14-P$2)") (class "Default")
      (node (ref "R14") (pin "1") (pinfunction "P$2_1") (pintype "bidirectional"))
      (node (ref "U1") (pin "P$26") (pinfunction "PIO2_2/DCD/MISO1_P$26") (pintype "bidirectional"))
    )
    (net (code "39") (name "Net-(R15-P$2)") (class "Default")
      (node (ref "D15") (pin "0") (pinfunction "0_0") (pintype "bidirectional"))
      (node (ref "R15") (pin "1") (pinfunction "P$2_1") (pintype "bidirectional"))
    )
    (net (code "40") (name "Net-(R16-P$2)") (class "Default")
      (node (ref "D14") (pin "0") (pinfunction "0_0") (pintype "bidirectional"))
      (node (ref "R16") (pin "1") (pinfunction "P$2_1") (pintype "bidirectional"))
    )
    (net (code "41") (name "Net-(R17-P$2)") (class "Default")
      (node (ref "D13") (pin "0") (pinfunction "0_0") (pintype "bidirectional"))
      (node (ref "R17") (pin "1") (pinfunction "P$2_1") (pintype "bidirectional"))
    )
    (net (code "42") (name "Net-(R18-P$2)") (class "Default")
      (node (ref "D12") (pin "0") (pinfunction "0_0") (pintype "bidirectional"))
      (node (ref "R18") (pin "1") (pinfunction "P$2_1") (pintype "bidirectional"))
    )
    (net (code "43") (name "Net-(R19-P$1)") (class "Default")
      (node (ref "D11") (pin "0") (pinfunction "0_0") (pintype "bidirectional"))
      (node (ref "R19") (pin "0") (pinfunction "P$1_0") (pintype "bidirectional"))
    )
    (net (code "44") (name "Net-(R20-P$2)") (class "Default")
      (node (ref "D10") (pin "0") (pinfunction "0_0") (pintype "bidirectional"))
      (node (ref "R20") (pin "1") (pinfunction "P$2_1") (pintype "bidirectional"))
    )
    (net (code "45") (name "Net-(R21-P$1)") (class "Default")
      (node (ref "R21") (pin "0") (pinfunction "P$1_0") (pintype "bidirectional"))
      (node (ref "U1") (pin "P$13") (pinfunction "PIO2_1/DSR/SCK1_P$13") (pintype "bidirectional"))
    )
    (net (code "46") (name "Net-(R21-P$2)") (class "Default")
      (node (ref "D3") (pin "0") (pinfunction "0_0") (pintype "bidirectional"))
      (node (ref "R21") (pin "1") (pinfunction "P$2_1") (pintype "bidirectional"))
    )
    (net (code "47") (name "Net-(R22-P$1)") (class "Default")
      (node (ref "D2") (pin "0") (pinfunction "0_0") (pintype "bidirectional"))
      (node (ref "R22") (pin "0") (pinfunction "P$1_0") (pintype "bidirectional"))
    )
    (net (code "48") (name "Net-(R23-P$2)") (class "Default")
      (node (ref "R23") (pin "1") (pinfunction "P$2_1") (pintype "bidirectional"))
      (node (ref "U$1") (pin "P$2") (pinfunction "P$2_P$2") (pintype "bidirectional"))
    )
    (net (code "49") (name "Net-(R24-P$2)") (class "Default")
      (node (ref "R24") (pin "1") (pinfunction "P$2_1") (pintype "bidirectional"))
      (node (ref "U$1") (pin "P$5") (pinfunction "P$5_P$5") (pintype "bidirectional"))
    )
    (net (code "50") (name "Net-(R25-P$2)") (class "Default")
      (node (ref "R25") (pin "1") (pinfunction "P$2_1") (pintype "bidirectional"))
      (node (ref "U$1") (pin "P$8") (pinfunction "P$8_P$8") (pintype "bidirectional"))
    )
    (net (code "51") (name "Net-(R29-P$2)") (class "Default")
      (node (ref "D9") (pin "0") (pinfunction "0_0") (pintype "bidirectional"))
      (node (ref "R29") (pin "1") (pinfunction "P$2_1") (pintype "bidirectional"))
    )
    (net (code "52") (name "Net-(R30-P$2)") (class "Default")
      (node (ref "D8") (pin "0") (pinfunction "0_0") (pintype "bidirectional"))
      (node (ref "R30") (pin "1") (pinfunction "P$2_1") (pintype "bidirectional"))
    )
    (net (code "53") (name "Net-(R31-P$1)") (class "Default")
      (node (ref "D7") (pin "0") (pinfunction "0_0") (pintype "bidirectional"))
      (node (ref "R31") (pin "0") (pinfunction "P$1_0") (pintype "bidirectional"))
    )
    (net (code "54") (name "Net-(R32-P$2)") (class "Default")
      (node (ref "D6") (pin "0") (pinfunction "0_0") (pintype "bidirectional"))
      (node (ref "R32") (pin "1") (pinfunction "P$2_1") (pintype "bidirectional"))
    )
    (net (code "55") (name "Net-(R33-P$2)") (class "Default")
      (node (ref "D5") (pin "0") (pinfunction "0_0") (pintype "bidirectional"))
      (node (ref "R33") (pin "1") (pinfunction "P$2_1") (pintype "bidirectional"))
    )
    (net (code "56") (name "Net-(R34-P$1)") (class "Default")
      (node (ref "D4") (pin "0") (pinfunction "0_0") (pintype "bidirectional"))
      (node (ref "R34") (pin "0") (pinfunction "P$1_0") (pintype "bidirectional"))
    )
    (net (code "57") (name "Net-(R35-P$1)") (class "Default")
      (node (ref "R35") (pin "0") (pinfunction "P$1_0") (pintype "bidirectional"))
      (node (ref "U1") (pin "P$14") (pinfunction "PIO0_3_P$14") (pintype "bidirectional"))
    )
    (net (code "58") (name "Net-(R40-P$2)") (class "Default")
      (node (ref "D22") (pin "0") (pinfunction "0_0") (pintype "bidirectional"))
      (node (ref "R40") (pin "1") (pinfunction "P$2_1") (pintype "bidirectional"))
    )
    (net (code "59") (name "Net-(R41-P$2)") (class "Default")
      (node (ref "D21") (pin "0") (pinfunction "0_0") (pintype "bidirectional"))
      (node (ref "R41") (pin "1") (pinfunction "P$2_1") (pintype "bidirectional"))
    )
    (net (code "60") (name "unconnected-(J3-+3V3-PadP$5)") (class "Default")
      (node (ref "J3") (pin "P$5") (pinfunction "+3V3_P$5") (pintype "bidirectional"))
    )
    (net (code "61") (name "unconnected-(U$1-PadP$10)") (class "Default")
      (node (ref "U$1") (pin "P$10") (pinfunction "P$10_P$10") (pintype "bidirectional"))
    )
    (net (code "62") (name "unconnected-(U1-PIO0_1{slash}CLKOUT{slash}CT32B0_MAT2{slash}ISP-PadP$4)") (class "Default")
      (node (ref "U1") (pin "P$4") (pinfunction "PIO0_1/CLKOUT/CT32B0_MAT2/ISP_P$4") (pintype "bidirectional"))
    )
    (net (code "63") (name "unconnected-(U1-PIO0_2{slash}SSEL0{slash}CT16B0_CAP0-PadP$10)") (class "Default")
      (node (ref "U1") (pin "P$10") (pinfunction "PIO0_2/SSEL0/CT16B0_CAP0_P$10") (pintype "bidirectional"))
    )
    (net (code "64") (name "unconnected-(U1-PIO0_4{slash}SCL-PadP$15)") (class "Default")
      (node (ref "U1") (pin "P$15") (pinfunction "PIO0_4/SCL_P$15") (pintype "bidirectional"))
    )
    (net (code "65") (name "unconnected-(U1-PIO0_5{slash}SDA-PadP$16)") (class "Default")
      (node (ref "U1") (pin "P$16") (pinfunction "PIO0_5/SDA_P$16") (pintype "bidirectional"))
    )
    (net (code "66") (name "unconnected-(U1-PIO0_7{slash}CTS-PadP$24)") (class "Default")
      (node (ref "U1") (pin "P$24") (pinfunction "PIO0_7/CTS_P$24") (pintype "bidirectional"))
    )
    (net (code "67") (name "unconnected-(U1-PIO0_9{slash}MOSI0{slash}CT16B0_MAT1-PadP$28)") (class "Default")
      (node (ref "U1") (pin "P$28") (pinfunction "PIO0_9/MOSI0/CT16B0_MAT1_P$28") (pintype "bidirectional"))
    )
    (net (code "68") (name "unconnected-(U1-PIO1_4{slash}AD5{slash}CT32B1_MAT3{slash}WAKEUP-PadP$40)") (class "Default")
      (node (ref "U1") (pin "P$40") (pinfunction "PIO1_4/AD5/CT32B1_MAT3/WAKEUP_P$40") (pintype "bidirectional"))
    )
    (net (code "69") (name "unconnected-(U1-PIO1_5{slash}RTS{slash}CT32B0_CAP0-PadP$45)") (class "Default")
      (node (ref "U1") (pin "P$45") (pinfunction "PIO1_5/RTS/CT32B0_CAP0_P$45") (pintype "bidirectional"))
    )
    (net (code "70") (name "unconnected-(U1-PIO1_8{slash}CT16B1_CAP0-PadP$9)") (class "Default")
      (node (ref "U1") (pin "P$9") (pinfunction "PIO1_8/CT16B1_CAP0_P$9") (pintype "bidirectional"))
    )
    (net (code "71") (name "unconnected-(U1-PIO1_10{slash}AD6{slash}CT16B1_MAT1-PadP$30)") (class "Default")
      (node (ref "U1") (pin "P$30") (pinfunction "PIO1_10/AD6/CT16B1_MAT1_P$30") (pintype "bidirectional"))
    )
    (net (code "72") (name "unconnected-(U1-PIO1_11{slash}AD7-PadP$42)") (class "Default")
      (node (ref "U1") (pin "P$42") (pinfunction "PIO1_11/AD7_P$42") (pintype "bidirectional"))
    )
    (net (code "73") (name "unconnected-(U1-PIO2_3{slash}RI{slash}MOSI1-PadP$38)") (class "Default")
      (node (ref "U1") (pin "P$38") (pinfunction "PIO2_3/RI/MOSI1_P$38") (pintype "bidirectional"))
    )
    (net (code "74") (name "unconnected-(U1-PIO2_6-PadP$1)") (class "Default")
      (node (ref "U1") (pin "P$1") (pinfunction "PIO2_6_P$1") (pintype "bidirectional"))
    )
    (net (code "75") (name "unconnected-(U1-PIO2_11{slash}SCK0-PadP$31)") (class "Default")
      (node (ref "U1") (pin "P$31") (pinfunction "PIO2_11/SCK0_P$31") (pintype "bidirectional"))
    )
    (net (code "76") (name "unconnected-(U1-PIO3_1{slash}DSR-PadP$37)") (class "Default")
      (node (ref "U1") (pin "P$37") (pinfunction "PIO3_1/DSR_P$37") (pintype "bidirectional"))
    )
    (net (code "77") (name "unconnected-(U1-PIO3_2{slash}DCD-PadP$43)") (class "Default")
      (node (ref "U1") (pin "P$43") (pinfunction "PIO3_2/DCD_P$43") (pintype "bidirectional"))
    )
    (net (code "78") (name "unconnected-(U1-R{slash}PIO1_2{slash}AD3{slash}CT32B1_MAT1-PadP$35)") (class "Default")
      (node (ref "U1") (pin "P$35") (pinfunction "R/PIO1_2/AD3/CT32B1_MAT1_P$35") (pintype "bidirectional"))
    )
    (net (code "79") (name "unconnected-(U1-SWCLK{slash}PIO0_10{slash}SCK0{slash}CT16B0_MAT2-PadP$29)") (class "Default")
      (node (ref "U1") (pin "P$29") (pinfunction "SWCLK/PIO0_10/SCK0/CT16B0_MAT2_P$29") (pintype "bidirectional"))
    )
    (net (code "80") (name "unconnected-(U1-SWDIO{slash}PIO1_3{slash}AD4{slash}CT32B1_MAT2-PadP$39)") (class "Default")
      (node (ref "U1") (pin "P$39") (pinfunction "SWDIO/PIO1_3/AD4/CT32B1_MAT2_P$39") (pintype "bidirectional"))
    )
    (net (code "81") (name "unconnected-(VR1-ON{slash}OFF-PadP$5)") (class "Default")
      (node (ref "VR1") (pin "P$5") (pinfunction "ON/OFF_P$5") (pintype "bidirectional"))
    )
    (net (code "82") (name "unconnected-(VR1-SS-PadP$2)") (class "Default")
      (node (ref "VR1") (pin "P$2") (pinfunction "SS_P$2") (pintype "bidirectional"))
    )
    (net (code "83") (name "unconnected-(VR1-SYNC-PadP$3)") (class "Default")
      (node (ref "VR1") (pin "P$3") (pinfunction "SYNC_P$3") (pintype "bidirectional"))
    )
  )
)
